# 02_-_HAB.net
KiCad netlist of a schematic drawn in Altium Designer
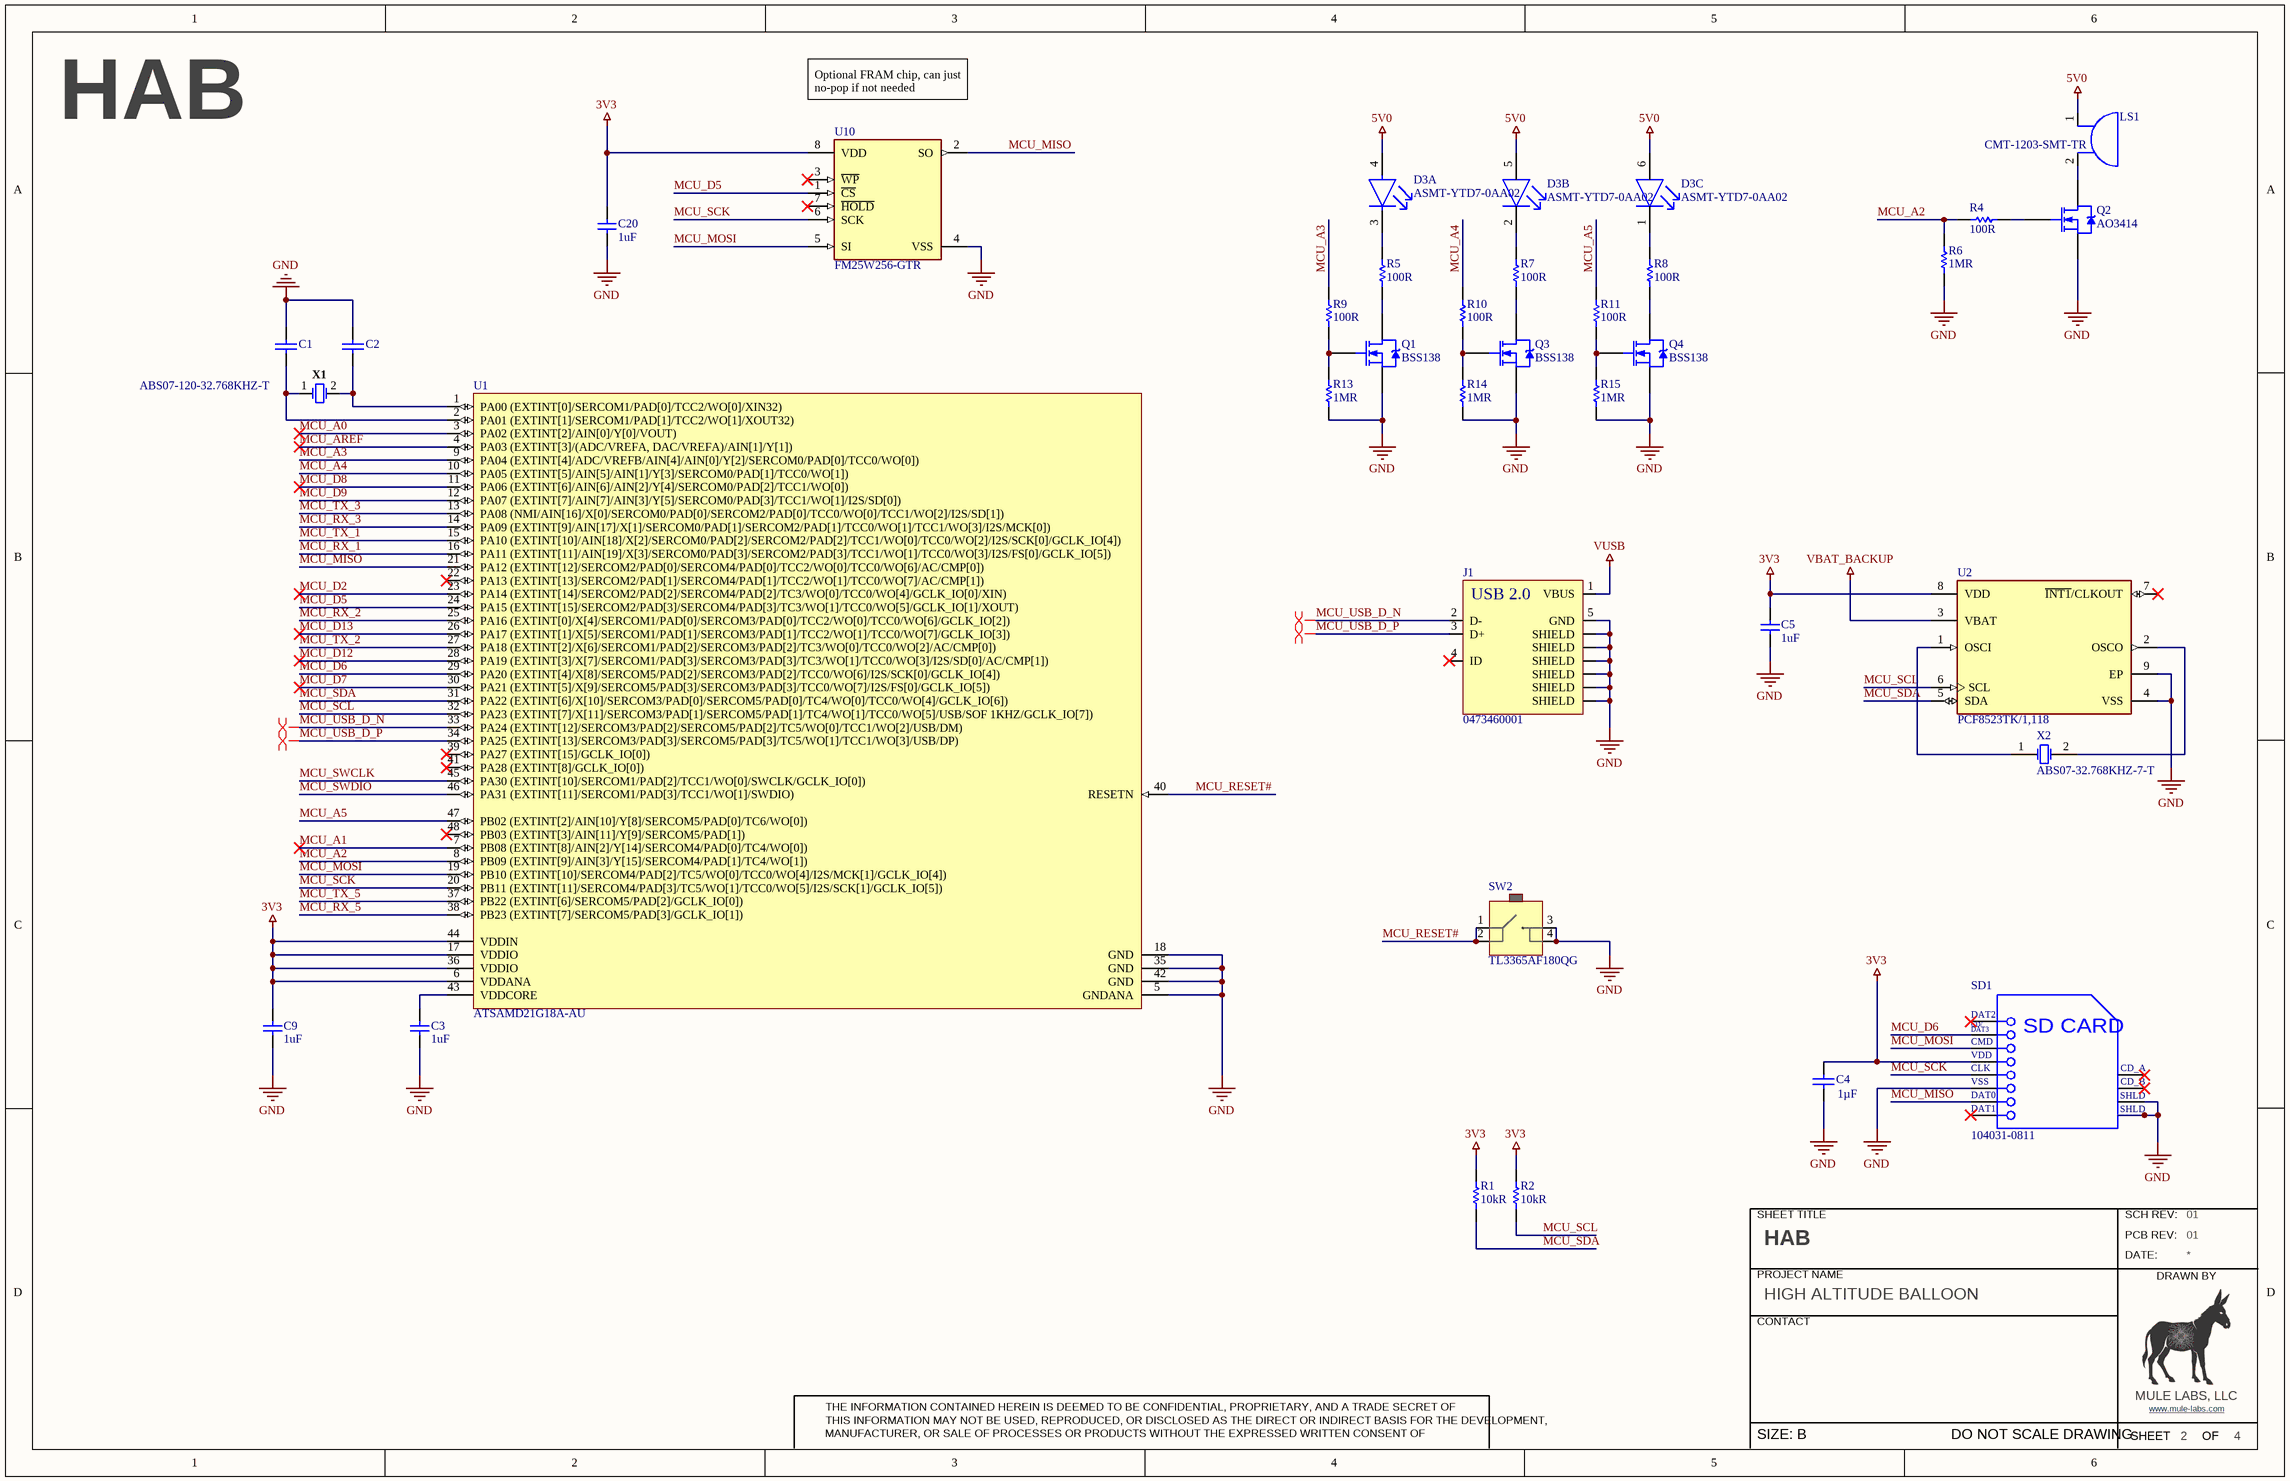
[diagram p0: [02] - HAB.SchDoc]

(export (version "E")
  (design (tool "Eeschema 10.0.6"))
  (components
    (comp (ref "C1")
      (value "GRM21A5C2E220JW01D")
      (footprint "CAPC2013X100X30ML20")
      (fields (field (name "MANUFACTURER") "Murata"))
      (libsource (lib "Altium Content Vault") (part "CAP"))
    )
    (comp (ref "C2")
      (value "GRM21A5C2E220JW01D")
      (footprint "CAPC2013X100X30ML20")
      (fields (field (name "MANUFACTURER") "Murata"))
      (libsource (lib "Altium Content Vault") (part "CAP"))
    )
    (comp (ref "C3")
      (value "1uF")
      (footprint "INCH 0805 - METRIC 2012 - H140")
      (description "CAP SMD 1uF 25V 10% 0805")
      (fields
        (field (name "MANUFACTURER") "Murata")
        (field (name "MANUFACTURER PART NUMBER") "GCM21BR71E105KA56L")
      )
      (libsource (lib "Capacitors") (part "GCM21BR71E105KA56L"))
    )
    (comp (ref "C4")
      (value "GRM21BR71C105KA01L")
      (footprint "CAPC2013X135X45ML10T25")
      (fields (field (name "CAPACITANCE") "1µF") (field (name "MANUFACTURER") "Murata"))
      (libsource (lib "Altium Content Vault") (part "CAP-NP-2"))
    )
    (comp (ref "C5")
      (value "1uF")
      (footprint "INCH 0805 - METRIC 2012 - H140")
      (description "CAP SMD 1uF 25V 10% 0805")
      (fields
        (field (name "MANUFACTURER") "Murata")
        (field (name "MANUFACTURER PART NUMBER") "GCM21BR71E105KA56L")
      )
      (libsource (lib "Capacitors") (part "GCM21BR71E105KA56L"))
    )
    (comp (ref "C9")
      (value "1uF")
      (footprint "INCH 0805 - METRIC 2012 - H140")
      (description "CAP SMD 1uF 25V 10% 0805")
      (fields
        (field (name "MANUFACTURER") "Murata")
        (field (name "MANUFACTURER PART NUMBER") "GCM21BR71E105KA56L")
      )
      (libsource (lib "Capacitors") (part "GCM21BR71E105KA56L"))
    )
    (comp (ref "C20")
      (value "1uF")
      (footprint "INCH 0805 - METRIC 2012 - H140")
      (description "CAP SMD 1uF 25V 10% 0805")
      (fields
        (field (name "MANUFACTURER") "Murata")
        (field (name "MANUFACTURER PART NUMBER") "GCM21BR71E105KA56L")
      )
      (libsource (lib "Capacitors") (part "GCM21BR71E105KA56L"))
    )
    (comp (ref "D3")
      (value "ASMT-YTD7-0AA02")
      (footprint "FP-PLCC-6-MFG")
      (description "LED RGB DIFFUSED 6PLCC SMD")
      (fields
        (field (name "MANUFACTURER") "Broadcom")
        (field (name "OCTOPART") "https://octopart.com/asmt-ytd7-0aa02-broadcom-71127359")
      )
      (libsource (lib "Altium Content Vault") (part "a8d7b0c4ab3168287692aa145c184e1"))
    )
    (comp (ref "J1")
      (value "0473460001")
      (footprint "MOLEX_047346-0001")
      (description "Conn Micro USB Type B RCP 5 POS 0.65mm Solder RA SMD 5 Terminal 1 Port Embossed T/R")
      (fields (field (name "MANUFACTURER") "Molex"))
      (libsource (lib "Connectors") (part "0473460001"))
    )
    (comp (ref "LS1")
      (value "CMT-1203-SMT-TR")
      (footprint "CMT-1203-SMT-TR")
      (description "AUDIO PIEZO TRANSDUCER 25V SMD")
      (fields (field (name "MANUFACTURER") "CUI"))
      (libsource (lib "Buzzers") (part "CMT-1203-SMT-TR"))
    )
    (comp (ref "Q1")
      (value "BSS138")
      (footprint "SOT95P240X120-3")
      (description "MOSFET N-CH 50V 220MA SOT-23")
      (fields (field (name "MANUFACTURER") "ON Semiconductor / Fairchild"))
      (libsource (lib "Transistors - FET") (part "BSS138"))
    )
    (comp (ref "Q2")
      (value "AO3414")
      (footprint "SOT95P240X120-3")
      (description "MOSFET N-CH 20V 4.2A SOT23")
      (fields (field (name "MANUFACTURER") "Alpha & Omega Semiconductor"))
      (libsource (lib "Transistors - FET") (part "AO3414"))
    )
    (comp (ref "Q3")
      (value "BSS138")
      (footprint "SOT95P240X120-3")
      (description "MOSFET N-CH 50V 220MA SOT-23")
      (fields (field (name "MANUFACTURER") "ON Semiconductor / Fairchild"))
      (libsource (lib "Transistors - FET") (part "BSS138"))
    )
    (comp (ref "Q4")
      (value "BSS138")
      (footprint "SOT95P240X120-3")
      (description "MOSFET N-CH 50V 220MA SOT-23")
      (fields (field (name "MANUFACTURER") "ON Semiconductor / Fairchild"))
      (libsource (lib "Transistors - FET") (part "BSS138"))
    )
    (comp (ref "R1")
      (value "10kR")
      (footprint "INCH 0805 - METRIC 2012 - H070")
      (description "RES SMD 10kOHM 1% 1/2W 0805")
      (fields
        (field (name "MANUFACTURER") "Panasonic")
        (field (name "MANUFACTURER PART NUMBER") "ERJ-P06F1002V")
      )
      (libsource (lib "Resistors") (part "ERJ-P06F1002V"))
    )
    (comp (ref "R2")
      (value "10kR")
      (footprint "INCH 0805 - METRIC 2012 - H070")
      (description "RES SMD 10kOHM 1% 1/2W 0805")
      (fields
        (field (name "MANUFACTURER") "Panasonic")
        (field (name "MANUFACTURER PART NUMBER") "ERJ-P06F1002V")
      )
      (libsource (lib "Resistors") (part "ERJ-P06F1002V"))
    )
    (comp (ref "R4")
      (value "100R")
      (footprint "INCH 0805 - METRIC 2012 - H070")
      (description "RES SMD 100 OHM 5% 1/2W 0805")
      (fields
        (field (name "MANUFACTURER") "Panasonic")
        (field (name "MANUFACTURER PART NUMBER") "ERJ-P06J101V")
      )
      (libsource (lib "Resistors") (part "ERJ-P06J101V"))
    )
    (comp (ref "R5")
      (value "100R")
      (footprint "INCH 0805 - METRIC 2012 - H070")
      (description "RES SMD 100 OHM 5% 1/2W 0805")
      (fields
        (field (name "MANUFACTURER") "Panasonic")
        (field (name "MANUFACTURER PART NUMBER") "ERJ-P06J101V")
      )
      (libsource (lib "Resistors") (part "ERJ-P06J101V"))
    )
    (comp (ref "R6")
      (value "1MR")
      (footprint "INCH 0805 - METRIC 2012 - H070")
      (description "Res Thick Film 0805 1M Ohm 5% 1/4W 200ppm/C Molded SMD SMD Punched Carrier T/R")
      (fields
        (field (name "MANUFACTURER") "Panasonic")
        (field (name "MANUFACTURER PART NUMBER") "ERJ-P06J105V")
      )
      (libsource (lib "Resistors") (part "ERJ-P06J105V"))
    )
    (comp (ref "R7")
      (value "100R")
      (footprint "INCH 0805 - METRIC 2012 - H070")
      (description "RES SMD 100 OHM 5% 1/2W 0805")
      (fields
        (field (name "MANUFACTURER") "Panasonic")
        (field (name "MANUFACTURER PART NUMBER") "ERJ-P06J101V")
      )
      (libsource (lib "Resistors") (part "ERJ-P06J101V"))
    )
    (comp (ref "R8")
      (value "100R")
      (footprint "INCH 0805 - METRIC 2012 - H070")
      (description "RES SMD 100 OHM 5% 1/2W 0805")
      (fields
        (field (name "MANUFACTURER") "Panasonic")
        (field (name "MANUFACTURER PART NUMBER") "ERJ-P06J101V")
      )
      (libsource (lib "Resistors") (part "ERJ-P06J101V"))
    )
    (comp (ref "R9")
      (value "100R")
      (footprint "INCH 0805 - METRIC 2012 - H070")
      (description "RES SMD 100 OHM 5% 1/2W 0805")
      (fields
        (field (name "MANUFACTURER") "Panasonic")
        (field (name "MANUFACTURER PART NUMBER") "ERJ-P06J101V")
      )
      (libsource (lib "Resistors") (part "ERJ-P06J101V"))
    )
    (comp (ref "R10")
      (value "100R")
      (footprint "INCH 0805 - METRIC 2012 - H070")
      (description "RES SMD 100 OHM 5% 1/2W 0805")
      (fields
        (field (name "MANUFACTURER") "Panasonic")
        (field (name "MANUFACTURER PART NUMBER") "ERJ-P06J101V")
      )
      (libsource (lib "Resistors") (part "ERJ-P06J101V"))
    )
    (comp (ref "R11")
      (value "100R")
      (footprint "INCH 0805 - METRIC 2012 - H070")
      (description "RES SMD 100 OHM 5% 1/2W 0805")
      (fields
        (field (name "MANUFACTURER") "Panasonic")
        (field (name "MANUFACTURER PART NUMBER") "ERJ-P06J101V")
      )
      (libsource (lib "Resistors") (part "ERJ-P06J101V"))
    )
    (comp (ref "R13")
      (value "1MR")
      (footprint "INCH 0805 - METRIC 2012 - H070")
      (description "Res Thick Film 0805 1M Ohm 5% 1/4W 200ppm/C Molded SMD SMD Punched Carrier T/R")
      (fields
        (field (name "MANUFACTURER") "Panasonic")
        (field (name "MANUFACTURER PART NUMBER") "ERJ-P06J105V")
      )
      (libsource (lib "Resistors") (part "ERJ-P06J105V"))
    )
    (comp (ref "R14")
      (value "1MR")
      (footprint "INCH 0805 - METRIC 2012 - H070")
      (description "Res Thick Film 0805 1M Ohm 5% 1/4W 200ppm/C Molded SMD SMD Punched Carrier T/R")
      (fields
        (field (name "MANUFACTURER") "Panasonic")
        (field (name "MANUFACTURER PART NUMBER") "ERJ-P06J105V")
      )
      (libsource (lib "Resistors") (part "ERJ-P06J105V"))
    )
    (comp (ref "R15")
      (value "1MR")
      (footprint "INCH 0805 - METRIC 2012 - H070")
      (description "Res Thick Film 0805 1M Ohm 5% 1/4W 200ppm/C Molded SMD SMD Punched Carrier T/R")
      (fields
        (field (name "MANUFACTURER") "Panasonic")
        (field (name "MANUFACTURER PART NUMBER") "ERJ-P06J105V")
      )
      (libsource (lib "Resistors") (part "ERJ-P06J105V"))
    )
    (comp (ref "SD1")
      (value "104031-0811")
      (footprint "MOLX-104031-0811_V")
      (description "Micro SD Card, RA, -25 to 85 degC, 8-Pin SMD, RoHS, Tape and Reel")
      (fields (field (name "MANUFACTURER") "Molex"))
      (libsource (lib "Altium Content Vault") (part "CN-SD-8-2SW-2S"))
    )
    (comp (ref "SW2")
      (value "TL3365AF180QG")
      (footprint "ESWITCH_TL3365AF180QG")
      (description "SWITCH TACTILE SPST-NO 0.05A 12V")
      (fields (field (name "MANUFACTURER") "E-Switch"))
      (libsource (lib "Switches") (part "TL3365AF180QG"))
    )
    (comp (ref "U1")
      (value "ATSAMD21G18A-AU")
      (footprint "ATML-TQFP48_M")
      (fields (field (name "MANUFACTURER") "Atmel"))
      (libsource (lib "Altium Content Vault") (part "ATML-ATSAMD21G18_17_16_15A-TQFP48"))
    )
    (comp (ref "U2")
      (value "PCF8523TK/1,118")
      (footprint "FP-SOT909-1-MFG")
      (description "IC RTC CLK/CALENDAR I2C 8-HVSON")
      (fields
        (field (name "MANUFACTURER") "NXP Semiconductors")
        (field (name "OCTOPART") "https://octopart.com/pcf8523tk%2F1%2C118-nxp+semiconductors-19647992")
      )
      (libsource (lib "Altium Content Vault") (part "fe0c3ba7f76caf909f8312b75f2dd76"))
    )
    (comp (ref "U10")
      (value "FM25W256-GTR")
      (footprint "FP-51-85066-MFG")
      (description "IC FRAM 256K SPI 20MHZ 8SOIC")
      (fields
        (field (name "MANUFACTURER") "Cypress Semiconductor")
        (field (name "OCTOPART") "https://octopart.com/fm25w256-gtr-cypress+semiconductor-25384375")
      )
      (libsource (lib "Altium Content Vault") (part "4525e9c5d1a5a2e555623125b0b88d8"))
    )
    (comp (ref "X1")
      (value "ABS07-120-32.768KHZ-T")
      (footprint "ABRA-ABS07_A_V")
      (description "Tuning Fork Crystal, 32.768 KHz, +/- 20 ppm, -40 to 85 degC, 2-Pin SMD, RoHS, Tape and Reel")
      (fields (field (name "MANUFACTURER") "Abracon") (field (name "TOLERANCE") "20ppm"))
      (libsource (lib "Altium Content Vault") (part "XTAL-1-2-2"))
    )
    (comp (ref "X2")
      (value "ABS07-32.768KHZ-7-T")
      (footprint "ABS07")
      (description "In a Pack of 10, Abracon 32.768kHz Crystal Unit ±20ppm SMD 2-Pin 3.2 x 1.5 x 0.9mm")
      (fields (field (name "MANUFACTURER") "Abracon") (field (name "TOLERANCE") "20ppm"))
      (libsource (lib "Crystals Oscillators Resonators") (part "ABS07-32.768KHZ-7-T"))
    )
  )
  (nets
    (net (code "1") (name "/MCU_A0") (class "Default")
      (node (ref "U1") (pin "3") (pinfunction "PA02_(EXTINT[2]/AIN[0]/Y[0]/VOUT)_3") (pintype "bidirectional+no_connect"))
    )
    (net (code "2") (name "/MCU_A1") (class "Default")
      (node (ref "U1") (pin "7") (pinfunction "PB08_(EXTINT[8]/AIN[2]/Y[14]/SERCOM4/PAD[0]/TC4/WO[0])_7") (pintype "bidirectional+no_connect"))
    )
    (net (code "3") (name "/MCU_A2") (class "Default")
      (node (ref "R4") (pin "1") (pintype "passive"))
      (node (ref "R6") (pin "2") (pintype "passive"))
      (node (ref "U1") (pin "8") (pinfunction "PB09_(EXTINT[9]/AIN[3]/Y[15]/SERCOM4/PAD[1]/TC4/WO[1])_8") (pintype "bidirectional"))
    )
    (net (code "4") (name "/MCU_A3") (class "Default")
      (node (ref "R9") (pin "2") (pintype "passive"))
      (node (ref "U1") (pin "9") (pinfunction "PA04_(EXTINT[4]/ADC/VREFB/AIN[4]/AIN[0]/Y[2]/SERCOM0/PAD[0]/TCC0/WO[0])_9") (pintype "bidirectional"))
    )
    (net (code "5") (name "/MCU_A4") (class "Default")
      (node (ref "R10") (pin "2") (pintype "passive"))
      (node (ref "U1") (pin "10") (pinfunction "PA05_(EXTINT[5]/AIN[5]/AIN[1]/Y[3]/SERCOM0/PAD[1]/TCC0/WO[1])_10") (pintype "bidirectional"))
    )
    (net (code "6") (name "/MCU_A5") (class "Default")
      (node (ref "R11") (pin "2") (pintype "passive"))
      (node (ref "U1") (pin "47") (pinfunction "PB02_(EXTINT[2]/AIN[10]/Y[8]/SERCOM5/PAD[0]/TC6/WO[0])_47") (pintype "bidirectional"))
    )
    (net (code "7") (name "/MCU_AREF") (class "Default")
      (node (ref "U1") (pin "4") (pinfunction "PA03_(EXTINT[3]/(ADC/VREFA,_DAC/VREFA)/AIN[1]/Y[1])_4") (pintype "bidirectional+no_connect"))
    )
    (net (code "8") (name "/MCU_D2") (class "Default")
      (node (ref "U1") (pin "23") (pinfunction "PA14_(EXTINT[14]/SERCOM2/PAD[2]/SERCOM4/PAD[2]/TC3/WO[0]/TCC0/WO[4]/GCLK_IO[0]/XIN)_23") (pintype "bidirectional+no_connect"))
    )
    (net (code "9") (name "/MCU_D5") (class "Default")
      (node (ref "U1") (pin "24") (pinfunction "PA15_(EXTINT[15]/SERCOM2/PAD[3]/SERCOM4/PAD[3]/TC3/WO[1]/TCC0/WO[5]/GCLK_IO[1]/XOUT)_24") (pintype "bidirectional"))
      (node (ref "U10") (pin "1") (pinfunction "~{CS}_1") (pintype "input"))
    )
    (net (code "10") (name "/MCU_D6") (class "Default")
      (node (ref "SD1") (pin "2") (pinfunction "CMD_2") (pintype "passive"))
      (node (ref "U1") (pin "29") (pinfunction "PA20_(EXTINT[4]/X[8]/SERCOM5/PAD[2]/SERCOM3/PAD[2]/TCC0/WO[6]/I2S/SCK[0]/GCLK_IO[4])_29") (pintype "bidirectional"))
    )
    (net (code "11") (name "/MCU_D7") (class "Default")
      (node (ref "U1") (pin "30") (pinfunction "PA21_(EXTINT[5]/X[9]/SERCOM5/PAD[3]/SERCOM3/PAD[3]/TCC0/WO[7]/I2S/FS[0]/GCLK_IO[5])_30") (pintype "bidirectional+no_connect"))
    )
    (net (code "12") (name "/MCU_D8") (class "Default")
      (node (ref "U1") (pin "11") (pinfunction "PA06_(EXTINT[6]/AIN[6]/AIN[2]/Y[4]/SERCOM0/PAD[2]/TCC1/WO[0])_11") (pintype "bidirectional+no_connect"))
    )
    (net (code "13") (name "/MCU_D9") (class "Default")
      (node (ref "U1") (pin "12") (pinfunction "PA07_(EXTINT[7]/AIN[7]/AIN[3]/Y[5]/SERCOM0/PAD[3]/TCC1/WO[1]/I2S/SD[0])_12") (pintype "bidirectional"))
    )
    (net (code "14") (name "/MCU_D12") (class "Default")
      (node (ref "U1") (pin "28") (pinfunction "PA19_(EXTINT[3]/X[7]/SERCOM1/PAD[3]/SERCOM3/PAD[3]/TC3/WO[1]/TCC0/WO[3]/I2S/SD[0]/AC/CMP[1])_28") (pintype "bidirectional+no_connect"))
    )
    (net (code "15") (name "/MCU_D13") (class "Default")
      (node (ref "U1") (pin "26") (pinfunction "PA17_(EXTINT[1]/X[5]/SERCOM1/PAD[1]/SERCOM3/PAD[1]/TCC2/WO[1]/TCC0/WO[7]/GCLK_IO[3])_26") (pintype "bidirectional+no_connect"))
    )
    (net (code "16") (name "/MCU_MISO") (class "Default")
      (node (ref "SD1") (pin "7") (pinfunction "DAT0_7") (pintype "passive"))
      (node (ref "U1") (pin "21") (pinfunction "PA12_(EXTINT[12]/SERCOM2/PAD[0]/SERCOM4/PAD[0]/TCC2/WO[0]/TCC0/WO[6]/AC/CMP[0])_21") (pintype "bidirectional"))
      (node (ref "U10") (pin "2") (pinfunction "SO_2") (pintype "output"))
    )
    (net (code "17") (name "/MCU_MOSI") (class "Default")
      (node (ref "SD1") (pin "3") (pinfunction "VSS1_3") (pintype "passive"))
      (node (ref "U1") (pin "19") (pinfunction "PB10_(EXTINT[10]/SERCOM4/PAD[2]/TC5/WO[0]/TCC0/WO[4]/I2S/MCK[1]/GCLK_IO[4])_19") (pintype "bidirectional"))
      (node (ref "U10") (pin "5") (pinfunction "SI_5") (pintype "input"))
    )
    (net (code "18") (name "/MCU_RESET#") (class "Default")
      (node (ref "SW2") (pin "1") (pinfunction "1_1") (pintype "passive"))
      (node (ref "SW2") (pin "2") (pinfunction "2_2") (pintype "passive"))
      (node (ref "U1") (pin "40") (pinfunction "RESETN_40") (pintype "input"))
    )
    (net (code "19") (name "/MCU_RX_1") (class "Default")
      (node (ref "U1") (pin "16") (pinfunction "PA11_(EXTINT[11]/AIN[19]/X[3]/SERCOM0/PAD[3]/SERCOM2/PAD[3]/TCC1/WO[1]/TCC0/WO[3]/I2S/FS[0]/GCLK_IO[5])_16") (pintype "bidirectional"))
    )
    (net (code "20") (name "/MCU_RX_2") (class "Default")
      (node (ref "U1") (pin "25") (pinfunction "PA16_(EXTINT[0]/X[4]/SERCOM1/PAD[0]/SERCOM3/PAD[0]/TCC2/WO[0]/TCC0/WO[6]/GCLK_IO[2])_25") (pintype "bidirectional"))
    )
    (net (code "21") (name "/MCU_RX_3") (class "Default")
      (node (ref "U1") (pin "14") (pinfunction "PA09_(EXTINT[9]/AIN[17]/X[1]/SERCOM0/PAD[1]/SERCOM2/PAD[1]/TCC0/WO[1]/TCC1/WO[3]/I2S/MCK[0])_14") (pintype "bidirectional"))
    )
    (net (code "22") (name "/MCU_RX_5") (class "Default")
      (node (ref "U1") (pin "38") (pinfunction "PB23_(EXTINT[7]/SERCOM5/PAD[3]/GCLK_IO[1])_38") (pintype "bidirectional"))
    )
    (net (code "23") (name "/MCU_SCK") (class "Default")
      (node (ref "SD1") (pin "5") (pinfunction "CLK_5") (pintype "passive"))
      (node (ref "U1") (pin "20") (pinfunction "PB11_(EXTINT[11]/SERCOM4/PAD[3]/TC5/WO[1]/TCC0/WO[5]/I2S/SCK[1]/GCLK_IO[5])_20") (pintype "bidirectional"))
      (node (ref "U10") (pin "6") (pinfunction "SCK_6") (pintype "input"))
    )
    (net (code "24") (name "/MCU_SCL") (class "Default")
      (node (ref "R2") (pin "1") (pintype "passive"))
      (node (ref "U1") (pin "32") (pinfunction "PA23_(EXTINT[7]/X[11]/SERCOM3/PAD[1]/SERCOM5/PAD[1]/TC4/WO[1]/TCC0/WO[5]/USB/SOF_1KHZ/GCLK_IO[7])_32") (pintype "bidirectional"))
      (node (ref "U2") (pin "6") (pinfunction "SCL_6") (pintype "input"))
    )
    (net (code "25") (name "/MCU_SDA") (class "Default")
      (node (ref "R1") (pin "1") (pintype "passive"))
      (node (ref "U1") (pin "31") (pinfunction "PA22_(EXTINT[6]/X[10]/SERCOM3/PAD[0]/SERCOM5/PAD[0]/TC4/WO[0]/TCC0/WO[4]/GCLK_IO[6])_31") (pintype "bidirectional"))
      (node (ref "U2") (pin "5") (pinfunction "SDA_5") (pintype "bidirectional"))
    )
    (net (code "26") (name "/MCU_SWCLK") (class "Default")
      (node (ref "U1") (pin "45") (pinfunction "PA30_(EXTINT[10]/SERCOM1/PAD[2]/TCC1/WO[0]/SWCLK/GCLK_IO[0])_45") (pintype "bidirectional"))
    )
    (net (code "27") (name "/MCU_SWDIO") (class "Default")
      (node (ref "U1") (pin "46") (pinfunction "PA31_(EXTINT[11]/SERCOM1/PAD[3]/TCC1/WO[1]/SWDIO)_46") (pintype "bidirectional"))
    )
    (net (code "28") (name "/MCU_TX_1") (class "Default")
      (node (ref "U1") (pin "15") (pinfunction "PA10_(EXTINT[10]/AIN[18]/X[2]/SERCOM0/PAD[2]/SERCOM2/PAD[2]/TCC1/WO[0]/TCC0/WO[2]/I2S/SCK[0]/GCLK_IO[4])_15") (pintype "bidirectional"))
    )
    (net (code "29") (name "/MCU_TX_2") (class "Default")
      (node (ref "U1") (pin "27") (pinfunction "PA18_(EXTINT[2]/X[6]/SERCOM1/PAD[2]/SERCOM3/PAD[2]/TC3/WO[0]/TCC0/WO[2]/AC/CMP[0])_27") (pintype "bidirectional"))
    )
    (net (code "30") (name "/MCU_TX_3") (class "Default")
      (node (ref "U1") (pin "13") (pinfunction "PA08_(NMI/AIN[16]/X[0]/SERCOM0/PAD[0]/SERCOM2/PAD[0]/TCC0/WO[0]/TCC1/WO[2]/I2S/SD[1])_13") (pintype "bidirectional"))
    )
    (net (code "31") (name "/MCU_TX_5") (class "Default")
      (node (ref "U1") (pin "37") (pinfunction "PB22_(EXTINT[6]/SERCOM5/PAD[2]/GCLK_IO[0])_37") (pintype "bidirectional"))
    )
    (net (code "32") (name "/MCU_USB_D_N") (class "Default")
      (node (ref "J1") (pin "2") (pinfunction "D-_2") (pintype "passive"))
      (node (ref "U1") (pin "33") (pinfunction "PA24_(EXTINT[12]/SERCOM3/PAD[2]/SERCOM5/PAD[2]/TC5/WO[0]/TCC1/WO[2]/USB/DM)_33") (pintype "bidirectional"))
    )
    (net (code "33") (name "/MCU_USB_D_P") (class "Default")
      (node (ref "J1") (pin "3") (pinfunction "D+_3") (pintype "passive"))
      (node (ref "U1") (pin "34") (pinfunction "PA25_(EXTINT[13]/SERCOM3/PAD[3]/SERCOM5/PAD[3]/TC5/WO[1]/TCC1/WO[3]/USB/DP)_34") (pintype "bidirectional"))
    )
    (net (code "34") (name "3V3") (class "Default")
      (node (ref "C20") (pin "2") (pintype "passive"))
      (node (ref "C4") (pin "1") (pinfunction "1_1") (pintype "passive"))
      (node (ref "C5") (pin "2") (pintype "passive"))
      (node (ref "C9") (pin "2") (pintype "passive"))
      (node (ref "R1") (pin "2") (pintype "passive"))
      (node (ref "R2") (pin "2") (pintype "passive"))
      (node (ref "SD1") (pin "4") (pinfunction "VDD_4") (pintype "passive"))
      (node (ref "U1") (pin "17") (pinfunction "VDDIO_17") (pintype "power_in"))
      (node (ref "U1") (pin "36") (pinfunction "VDDIO_36") (pintype "power_in"))
      (node (ref "U1") (pin "44") (pinfunction "VDDIN_44") (pintype "power_in"))
      (node (ref "U1") (pin "6") (pinfunction "VDDANA_6") (pintype "power_in"))
      (node (ref "U10") (pin "8") (pinfunction "VDD_8") (pintype "power_in"))
      (node (ref "U2") (pin "8") (pinfunction "VDD_8") (pintype "power_in"))
    )
    (net (code "35") (name "5V0") (class "Default")
      (node (ref "D3") (pin "4") (pinfunction "Anode(Red)_4") (pintype "passive"))
      (node (ref "D3") (pin "5") (pinfunction "Anode(Green)_5") (pintype "passive"))
      (node (ref "D3") (pin "6") (pinfunction "Anode(Blue)_6") (pintype "passive"))
      (node (ref "LS1") (pin "1") (pintype "passive"))
    )
    (net (code "36") (name "GND") (class "Default")
      (node (ref "C1") (pin "2") (pinfunction "2_2") (pintype "passive"))
      (node (ref "C2") (pin "2") (pinfunction "2_2") (pintype "passive"))
      (node (ref "C20") (pin "1") (pintype "passive"))
      (node (ref "C3") (pin "1") (pintype "passive"))
      (node (ref "C4") (pin "2") (pinfunction "2_2") (pintype "passive"))
      (node (ref "C5") (pin "1") (pintype "passive"))
      (node (ref "C9") (pin "1") (pintype "passive"))
      (node (ref "J1") (pin "0") (pinfunction "SHIELD_0") (pintype "passive"))
      (node (ref "J1") (pin "5") (pinfunction "GND_5") (pintype "passive"))
      (node (ref "Q1") (pin "2") (pinfunction "S_2") (pintype "passive"))
      (node (ref "Q2") (pin "2") (pinfunction "S_2") (pintype "passive"))
      (node (ref "Q3") (pin "2") (pinfunction "S_2") (pintype "passive"))
      (node (ref "Q4") (pin "2") (pinfunction "S_2") (pintype "passive"))
      (node (ref "R13") (pin "1") (pintype "passive"))
      (node (ref "R14") (pin "1") (pintype "passive"))
      (node (ref "R15") (pin "1") (pintype "passive"))
      (node (ref "R6") (pin "1") (pintype "passive"))
      (node (ref "SD1") (pin "11") (pinfunction "SHLD1_11") (pintype "passive"))
      (node (ref "SD1") (pin "12") (pinfunction "SHLD2_12") (pintype "passive"))
      (node (ref "SD1") (pin "6") (pinfunction "VSS2_6") (pintype "passive"))
      (node (ref "SW2") (pin "3") (pinfunction "3_3") (pintype "passive"))
      (node (ref "SW2") (pin "4") (pinfunction "4_4") (pintype "passive"))
      (node (ref "U1") (pin "18") (pinfunction "GND_18") (pintype "power_in"))
      (node (ref "U1") (pin "35") (pinfunction "GND_35") (pintype "power_in"))
      (node (ref "U1") (pin "42") (pinfunction "GND_42") (pintype "power_in"))
      (node (ref "U1") (pin "5") (pinfunction "GNDANA_5") (pintype "power_in"))
      (node (ref "U10") (pin "4") (pinfunction "VSS_4") (pintype "power_in"))
      (node (ref "U2") (pin "4") (pinfunction "VSS_4") (pintype "power_in"))
      (node (ref "U2") (pin "9") (pinfunction "EP_9") (pintype "passive"))
    )
    (net (code "37") (name "Net-(D3A-Cathode(Red))") (class "Default")
      (node (ref "D3") (pin "3") (pinfunction "Cathode(Red)_3") (pintype "passive"))
      (node (ref "R5") (pin "2") (pintype "passive"))
    )
    (net (code "38") (name "Net-(D3B-Cathode(Green))") (class "Default")
      (node (ref "D3") (pin "2") (pinfunction "Cathode(Green)_2") (pintype "passive"))
      (node (ref "R7") (pin "2") (pintype "passive"))
    )
    (net (code "39") (name "Net-(D3C-Cathode(Blue))") (class "Default")
      (node (ref "D3") (pin "1") (pinfunction "Cathode(Blue)_1") (pintype "passive"))
      (node (ref "R8") (pin "2") (pintype "passive"))
    )
    (net (code "40") (name "Net-(Q1-D)") (class "Default")
      (node (ref "Q1") (pin "3") (pinfunction "D_3") (pintype "passive"))
      (node (ref "R5") (pin "1") (pintype "passive"))
    )
    (net (code "41") (name "Net-(Q1-G)") (class "Default")
      (node (ref "Q1") (pin "1") (pinfunction "G_1") (pintype "passive"))
      (node (ref "R13") (pin "2") (pintype "passive"))
      (node (ref "R9") (pin "1") (pintype "passive"))
    )
    (net (code "42") (name "Net-(Q2-D)") (class "Default")
      (node (ref "LS1") (pin "2") (pintype "passive"))
      (node (ref "Q2") (pin "3") (pinfunction "D_3") (pintype "passive"))
    )
    (net (code "43") (name "Net-(Q2-G)") (class "Default")
      (node (ref "Q2") (pin "1") (pinfunction "G_1") (pintype "passive"))
      (node (ref "R4") (pin "2") (pintype "passive"))
    )
    (net (code "44") (name "Net-(Q3-D)") (class "Default")
      (node (ref "Q3") (pin "3") (pinfunction "D_3") (pintype "passive"))
      (node (ref "R7") (pin "1") (pintype "passive"))
    )
    (net (code "45") (name "Net-(Q3-G)") (class "Default")
      (node (ref "Q3") (pin "1") (pinfunction "G_1") (pintype "passive"))
      (node (ref "R10") (pin "1") (pintype "passive"))
      (node (ref "R14") (pin "2") (pintype "passive"))
    )
    (net (code "46") (name "Net-(Q4-D)") (class "Default")
      (node (ref "Q4") (pin "3") (pinfunction "D_3") (pintype "passive"))
      (node (ref "R8") (pin "1") (pintype "passive"))
    )
    (net (code "47") (name "Net-(Q4-G)") (class "Default")
      (node (ref "Q4") (pin "1") (pinfunction "G_1") (pintype "passive"))
      (node (ref "R11") (pin "1") (pintype "passive"))
      (node (ref "R15") (pin "2") (pintype "passive"))
    )
    (net (code "48") (name "Net-(U1-PA00_(EXTINT[0]{slash}SERCOM1{slash}PAD[0]{slash}TCC2{slash}WO[0]{slash}XIN32))") (class "Default")
      (node (ref "C2") (pin "1") (pinfunction "1_1") (pintype "passive"))
      (node (ref "U1") (pin "1") (pinfunction "PA00_(EXTINT[0]/SERCOM1/PAD[0]/TCC2/WO[0]/XIN32)_1") (pintype "bidirectional"))
      (node (ref "X1") (pin "2") (pinfunction "2_2") (pintype "passive"))
    )
    (net (code "49") (name "Net-(U1-PA01_(EXTINT[1]{slash}SERCOM1{slash}PAD[1]{slash}TCC2{slash}WO[1]{slash}XOUT32))") (class "Default")
      (node (ref "C1") (pin "1") (pinfunction "1_1") (pintype "passive"))
      (node (ref "U1") (pin "2") (pinfunction "PA01_(EXTINT[1]/SERCOM1/PAD[1]/TCC2/WO[1]/XOUT32)_2") (pintype "bidirectional"))
      (node (ref "X1") (pin "1") (pinfunction "1_1") (pintype "passive"))
    )
    (net (code "50") (name "Net-(U1-VDDCORE)") (class "Default")
      (node (ref "C3") (pin "2") (pintype "passive"))
      (node (ref "U1") (pin "43") (pinfunction "VDDCORE_43") (pintype "power_in"))
    )
    (net (code "51") (name "Net-(U2-OSCI)") (class "Default")
      (node (ref "U2") (pin "1") (pinfunction "OSCI_1") (pintype "input"))
      (node (ref "X2") (pin "1") (pinfunction "OSC1_1") (pintype "passive"))
    )
    (net (code "52") (name "Net-(U2-OSCO)") (class "Default")
      (node (ref "U2") (pin "2") (pinfunction "OSCO_2") (pintype "output"))
      (node (ref "X2") (pin "2") (pinfunction "OSC2_2") (pintype "passive"))
    )
    (net (code "53") (name "VBAT_BACKUP") (class "Default")
      (node (ref "U2") (pin "3") (pinfunction "VBAT_3") (pintype "power_in"))
    )
    (net (code "54") (name "VUSB") (class "Default")
      (node (ref "J1") (pin "1") (pinfunction "VBUS_1") (pintype "passive"))
    )
    (net (code "55") (name "unconnected-(J1-ID-Pad4)") (class "Default")
      (node (ref "J1") (pin "4") (pinfunction "ID_4") (pintype "passive+no_connect"))
    )
    (net (code "56") (name "unconnected-(SD1-CD_A-Pad9)") (class "Default")
      (node (ref "SD1") (pin "9") (pinfunction "CD_A_9") (pintype "passive+no_connect"))
    )
    (net (code "57") (name "unconnected-(SD1-CD_B-Pad10)") (class "Default")
      (node (ref "SD1") (pin "10") (pinfunction "CD_B_10") (pintype "passive+no_connect"))
    )
    (net (code "58") (name "unconnected-(SD1-CD{slash}DAT3-Pad1)") (class "Default")
      (node (ref "SD1") (pin "1") (pinfunction "CD/DAT3_1") (pintype "passive+no_connect"))
    )
    (net (code "59") (name "unconnected-(SD1-DAT1-Pad8)") (class "Default")
      (node (ref "SD1") (pin "8") (pinfunction "DAT1_8") (pintype "passive+no_connect"))
    )
    (net (code "60") (name "unconnected-(U1-PA13_(EXTINT[13]{slash}SERCOM2{slash}PAD[1]{slash}SERCOM4{slash}PAD[1]{slash}TCC2{slash}WO[1]{slash}TCC0{slash}WO[7]{slash}AC{slash}CMP[1])-Pad22)") (class "Default")
      (node (ref "U1") (pin "22") (pinfunction "PA13_(EXTINT[13]/SERCOM2/PAD[1]/SERCOM4/PAD[1]/TCC2/WO[1]/TCC0/WO[7]/AC/CMP[1])_22") (pintype "bidirectional+no_connect"))
    )
    (net (code "61") (name "unconnected-(U1-PA27_(EXTINT[15]{slash}GCLK_IO[0])-Pad39)") (class "Default")
      (node (ref "U1") (pin "39") (pinfunction "PA27_(EXTINT[15]/GCLK_IO[0])_39") (pintype "bidirectional+no_connect"))
    )
    (net (code "62") (name "unconnected-(U1-PA28_(EXTINT[8]{slash}GCLK_IO[0])-Pad41)") (class "Default")
      (node (ref "U1") (pin "41") (pinfunction "PA28_(EXTINT[8]/GCLK_IO[0])_41") (pintype "bidirectional+no_connect"))
    )
    (net (code "63") (name "unconnected-(U1-PB03_(EXTINT[3]{slash}AIN[11]{slash}Y[9]{slash}SERCOM5{slash}PAD[1])-Pad48)") (class "Default")
      (node (ref "U1") (pin "48") (pinfunction "PB03_(EXTINT[3]/AIN[11]/Y[9]/SERCOM5/PAD[1])_48") (pintype "bidirectional+no_connect"))
    )
    (net (code "64") (name "unconnected-(U2-~{INT1}{slash}CLKOUT-Pad7)") (class "Default")
      (node (ref "U2") (pin "7") (pinfunction "~{INT1}/CLKOUT_7") (pintype "bidirectional+no_connect"))
    )
    (net (code "65") (name "unconnected-(U10-~{HOLD}-Pad7)") (class "Default")
      (node (ref "U10") (pin "7") (pinfunction "~{HOLD}_7") (pintype "input+no_connect"))
    )
    (net (code "66") (name "unconnected-(U10-~{WP}-Pad3)") (class "Default")
      (node (ref "U10") (pin "3") (pinfunction "~{WP}_3") (pintype "input+no_connect"))
    )
  )
)
